# gadget_pcb.net
KiCad netlist of a schematic drawn in EAGLE
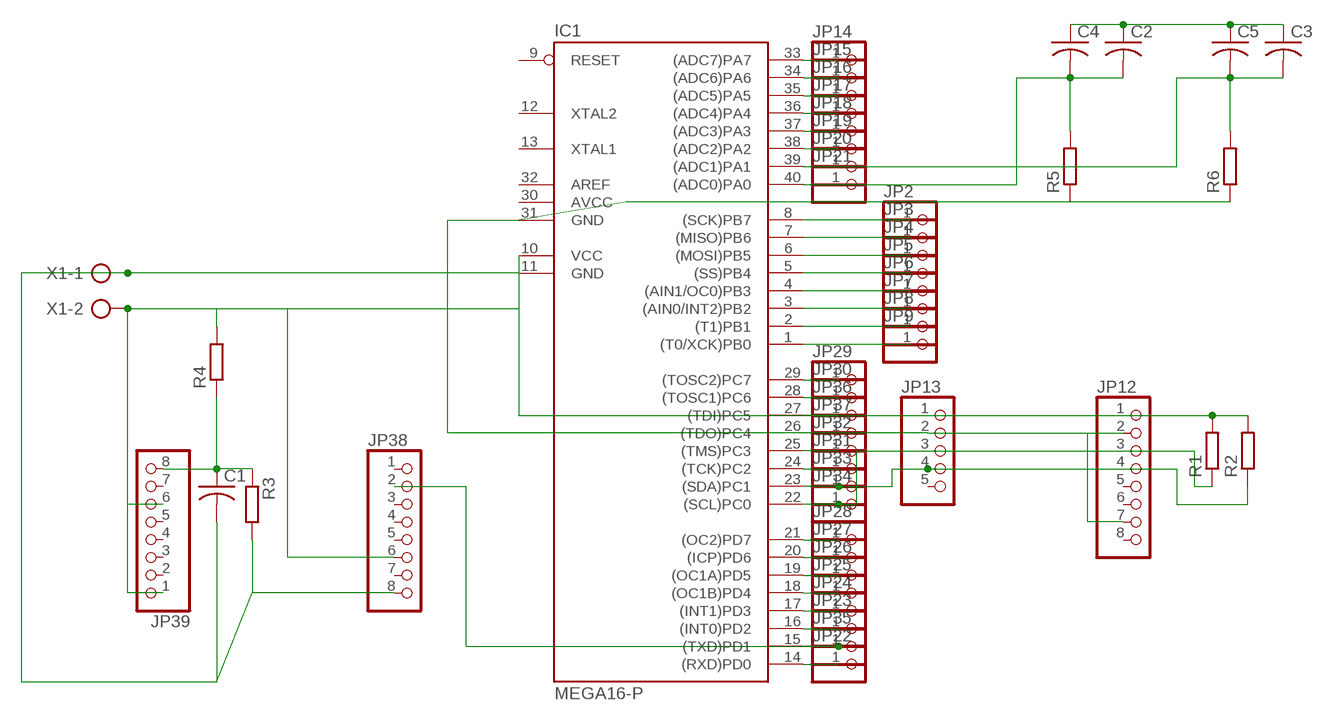
[diagram p0: schematic, sheet 1]

(export (version "E")
  (design (tool "Eeschema 10.0.6"))
  (components
    (comp (ref "C1")
      (value "C-US050-024X044")
      (footprint "eagle-import:C050-024X044")
      (libsource (lib "eagle-import") (part "C-US050-024X044"))
    )
    (comp (ref "C2")
      (value "C-US050-024X044")
      (footprint "eagle-import:C050-024X044")
      (libsource (lib "eagle-import") (part "C-US050-024X044"))
    )
    (comp (ref "C3")
      (value "C-US050-024X044")
      (footprint "eagle-import:C050-024X044")
      (libsource (lib "eagle-import") (part "C-US050-024X044"))
    )
    (comp (ref "C4")
      (value "C-US050-045X075")
      (footprint "eagle-import:C050-045X075")
      (libsource (lib "eagle-import") (part "C-US050-045X075"))
    )
    (comp (ref "C5")
      (value "C-US050-045X075")
      (footprint "eagle-import:C050-045X075")
      (libsource (lib "eagle-import") (part "C-US050-045X075"))
    )
    (comp (ref "IC1")
      (value "MEGA16-P")
      (footprint "eagle-import:DIL40")
      (fields (field (name "MPN") "ATMEGA16-16PU"))
      (libsource (lib "eagle-import") (part "MEGA16-P"))
    )
    (comp (ref "JP2")
      (value "PINHD-1X1")
      (footprint "eagle-import:1X01")
      (libsource (lib "eagle-import") (part "PINHD-1X1"))
    )
    (comp (ref "JP3")
      (value "PINHD-1X1")
      (footprint "eagle-import:1X01")
      (libsource (lib "eagle-import") (part "PINHD-1X1"))
    )
    (comp (ref "JP4")
      (value "PINHD-1X1")
      (footprint "eagle-import:1X01")
      (libsource (lib "eagle-import") (part "PINHD-1X1"))
    )
    (comp (ref "JP5")
      (value "PINHD-1X1")
      (footprint "eagle-import:1X01")
      (libsource (lib "eagle-import") (part "PINHD-1X1"))
    )
    (comp (ref "JP6")
      (value "PINHD-1X1")
      (footprint "eagle-import:1X01")
      (libsource (lib "eagle-import") (part "PINHD-1X1"))
    )
    (comp (ref "JP7")
      (value "PINHD-1X1")
      (footprint "eagle-import:1X01")
      (libsource (lib "eagle-import") (part "PINHD-1X1"))
    )
    (comp (ref "JP8")
      (value "PINHD-1X1")
      (footprint "eagle-import:1X01")
      (libsource (lib "eagle-import") (part "PINHD-1X1"))
    )
    (comp (ref "JP9")
      (value "PINHD-1X1")
      (footprint "eagle-import:1X01")
      (libsource (lib "eagle-import") (part "PINHD-1X1"))
    )
    (comp (ref "JP12")
      (value "PINHD-1X8")
      (footprint "eagle-import:1X08")
      (libsource (lib "eagle-import") (part "PINHD-1X8"))
    )
    (comp (ref "JP13")
      (value "PINHD-1X5")
      (footprint "eagle-import:1X05")
      (libsource (lib "eagle-import") (part "PINHD-1X5"))
    )
    (comp (ref "JP14")
      (value "PINHD-1X1")
      (footprint "eagle-import:1X01")
      (libsource (lib "eagle-import") (part "PINHD-1X1"))
    )
    (comp (ref "JP15")
      (value "PINHD-1X1")
      (footprint "eagle-import:1X01")
      (libsource (lib "eagle-import") (part "PINHD-1X1"))
    )
    (comp (ref "JP16")
      (value "PINHD-1X1")
      (footprint "eagle-import:1X01")
      (libsource (lib "eagle-import") (part "PINHD-1X1"))
    )
    (comp (ref "JP17")
      (value "PINHD-1X1")
      (footprint "eagle-import:1X01")
      (libsource (lib "eagle-import") (part "PINHD-1X1"))
    )
    (comp (ref "JP18")
      (value "PINHD-1X1")
      (footprint "eagle-import:1X01")
      (libsource (lib "eagle-import") (part "PINHD-1X1"))
    )
    (comp (ref "JP19")
      (value "PINHD-1X1")
      (footprint "eagle-import:1X01")
      (libsource (lib "eagle-import") (part "PINHD-1X1"))
    )
    (comp (ref "JP20")
      (value "PINHD-1X1")
      (footprint "eagle-import:1X01")
      (libsource (lib "eagle-import") (part "PINHD-1X1"))
    )
    (comp (ref "JP21")
      (value "PINHD-1X1")
      (footprint "eagle-import:1X01")
      (libsource (lib "eagle-import") (part "PINHD-1X1"))
    )
    (comp (ref "JP22")
      (value "PINHD-1X1")
      (footprint "eagle-import:1X01")
      (libsource (lib "eagle-import") (part "PINHD-1X1"))
    )
    (comp (ref "JP23")
      (value "PINHD-1X1")
      (footprint "eagle-import:1X01")
      (libsource (lib "eagle-import") (part "PINHD-1X1"))
    )
    (comp (ref "JP24")
      (value "PINHD-1X1")
      (footprint "eagle-import:1X01")
      (libsource (lib "eagle-import") (part "PINHD-1X1"))
    )
    (comp (ref "JP25")
      (value "PINHD-1X1")
      (footprint "eagle-import:1X01")
      (libsource (lib "eagle-import") (part "PINHD-1X1"))
    )
    (comp (ref "JP26")
      (value "PINHD-1X1")
      (footprint "eagle-import:1X01")
      (libsource (lib "eagle-import") (part "PINHD-1X1"))
    )
    (comp (ref "JP27")
      (value "PINHD-1X1")
      (footprint "eagle-import:1X01")
      (libsource (lib "eagle-import") (part "PINHD-1X1"))
    )
    (comp (ref "JP28")
      (value "PINHD-1X1")
      (footprint "eagle-import:1X01")
      (libsource (lib "eagle-import") (part "PINHD-1X1"))
    )
    (comp (ref "JP29")
      (value "PINHD-1X1")
      (footprint "eagle-import:1X01")
      (libsource (lib "eagle-import") (part "PINHD-1X1"))
    )
    (comp (ref "JP30")
      (value "PINHD-1X1")
      (footprint "eagle-import:1X01")
      (libsource (lib "eagle-import") (part "PINHD-1X1"))
    )
    (comp (ref "JP31")
      (value "PINHD-1X1")
      (footprint "eagle-import:1X01")
      (libsource (lib "eagle-import") (part "PINHD-1X1"))
    )
    (comp (ref "JP32")
      (value "PINHD-1X1")
      (footprint "eagle-import:1X01")
      (libsource (lib "eagle-import") (part "PINHD-1X1"))
    )
    (comp (ref "JP33")
      (value "PINHD-1X1")
      (footprint "eagle-import:1X01")
      (libsource (lib "eagle-import") (part "PINHD-1X1"))
    )
    (comp (ref "JP34")
      (value "PINHD-1X1")
      (footprint "eagle-import:1X01")
      (libsource (lib "eagle-import") (part "PINHD-1X1"))
    )
    (comp (ref "JP35")
      (value "PINHD-1X1")
      (footprint "eagle-import:1X01")
      (libsource (lib "eagle-import") (part "PINHD-1X1"))
    )
    (comp (ref "JP36")
      (value "PINHD-1X1")
      (footprint "eagle-import:1X01")
      (libsource (lib "eagle-import") (part "PINHD-1X1"))
    )
    (comp (ref "JP37")
      (value "PINHD-1X1")
      (footprint "eagle-import:1X01")
      (libsource (lib "eagle-import") (part "PINHD-1X1"))
    )
    (comp (ref "JP38")
      (value "PINHD-1X8")
      (footprint "eagle-import:1X08")
      (libsource (lib "eagle-import") (part "PINHD-1X8"))
    )
    (comp (ref "JP39")
      (value "PINHD-1X8")
      (footprint "eagle-import:1X08")
      (libsource (lib "eagle-import") (part "PINHD-1X8"))
    )
    (comp (ref "R1")
      (value "R-EU_0207/10")
      (footprint "eagle-import:0207_10")
      (libsource (lib "eagle-import") (part "R-EU_0207/10"))
    )
    (comp (ref "R2")
      (value "R-EU_0207/10")
      (footprint "eagle-import:0207_10")
      (libsource (lib "eagle-import") (part "R-EU_0207/10"))
    )
    (comp (ref "R3")
      (value "R-EU_0207/5V")
      (footprint "eagle-import:0207_5V")
      (libsource (lib "eagle-import") (part "R-EU_0207/5V"))
    )
    (comp (ref "R4")
      (value "R-EU_0207/10")
      (footprint "eagle-import:0207_10")
      (libsource (lib "eagle-import") (part "R-EU_0207/10"))
    )
    (comp (ref "R5")
      (value "R-EU_0207/7")
      (footprint "eagle-import:0207_7")
      (libsource (lib "eagle-import") (part "R-EU_0207/7"))
    )
    (comp (ref "R6")
      (value "R-EU_0207/7")
      (footprint "eagle-import:0207_7")
      (libsource (lib "eagle-import") (part "R-EU_0207/7"))
    )
    (comp (ref "X1")
      (value "AK500/2")
      (footprint "eagle-import:AK500_2")
      (libsource (lib "eagle-import") (part "AK500/2"))
    )
  )
  (nets
    (net (code "1") (name "/AVCC") (class "Default")
      (node (ref "IC1") (pin "30") (pinfunction "AVCC_30") (pintype "power_in"))
    )
    (net (code "2") (name "Net-(C1-Pad1)") (class "Default")
      (node (ref "C1") (pin "1") (pinfunction "1_1") (pintype "passive"))
      (node (ref "JP39") (pin "8") (pinfunction "8_8") (pintype "passive"))
      (node (ref "R3") (pin "1") (pinfunction "1_1") (pintype "passive"))
      (node (ref "R4") (pin "1") (pinfunction "1_1") (pintype "passive"))
    )
    (net (code "3") (name "Net-(C2-Pad1)") (class "Default")
      (node (ref "C2") (pin "1") (pinfunction "1_1") (pintype "passive"))
      (node (ref "C3") (pin "1") (pinfunction "1_1") (pintype "passive"))
      (node (ref "C4") (pin "1") (pinfunction "1_1") (pintype "passive"))
      (node (ref "C5") (pin "1") (pinfunction "1_1") (pintype "passive"))
    )
    (net (code "4") (name "Net-(IC1-(ADC0)PA0)") (class "Default")
      (node (ref "C2") (pin "2") (pinfunction "2_2") (pintype "passive"))
      (node (ref "C4") (pin "2") (pinfunction "2_2") (pintype "passive"))
      (node (ref "IC1") (pin "40") (pinfunction "(ADC0)PA0_40") (pintype "bidirectional"))
      (node (ref "JP21") (pin "1") (pinfunction "1_1") (pintype "passive"))
      (node (ref "R5") (pin "2") (pinfunction "2_2") (pintype "passive"))
    )
    (net (code "5") (name "Net-(IC1-(ADC1)PA1)") (class "Default")
      (node (ref "C3") (pin "2") (pinfunction "2_2") (pintype "passive"))
      (node (ref "C5") (pin "2") (pinfunction "2_2") (pintype "passive"))
      (node (ref "IC1") (pin "39") (pinfunction "(ADC1)PA1_39") (pintype "bidirectional"))
      (node (ref "JP20") (pin "1") (pinfunction "1_1") (pintype "passive"))
      (node (ref "R6") (pin "2") (pinfunction "2_2") (pintype "passive"))
    )
    (net (code "6") (name "Net-(IC1-(ADC2)PA2)") (class "Default")
      (node (ref "IC1") (pin "38") (pinfunction "(ADC2)PA2_38") (pintype "bidirectional"))
      (node (ref "JP19") (pin "1") (pinfunction "1_1") (pintype "passive"))
    )
    (net (code "7") (name "Net-(IC1-(ADC3)PA3)") (class "Default")
      (node (ref "IC1") (pin "37") (pinfunction "(ADC3)PA3_37") (pintype "bidirectional"))
      (node (ref "JP18") (pin "1") (pinfunction "1_1") (pintype "passive"))
    )
    (net (code "8") (name "Net-(IC1-(ADC4)PA4)") (class "Default")
      (node (ref "IC1") (pin "36") (pinfunction "(ADC4)PA4_36") (pintype "bidirectional"))
      (node (ref "JP17") (pin "1") (pinfunction "1_1") (pintype "passive"))
    )
    (net (code "9") (name "Net-(IC1-(ADC5)PA5)") (class "Default")
      (node (ref "IC1") (pin "35") (pinfunction "(ADC5)PA5_35") (pintype "bidirectional"))
      (node (ref "JP16") (pin "1") (pinfunction "1_1") (pintype "passive"))
    )
    (net (code "10") (name "Net-(IC1-(ADC6)PA6)") (class "Default")
      (node (ref "IC1") (pin "34") (pinfunction "(ADC6)PA6_34") (pintype "bidirectional"))
      (node (ref "JP15") (pin "1") (pinfunction "1_1") (pintype "passive"))
    )
    (net (code "11") (name "Net-(IC1-(ADC7)PA7)") (class "Default")
      (node (ref "IC1") (pin "33") (pinfunction "(ADC7)PA7_33") (pintype "bidirectional"))
      (node (ref "JP14") (pin "1") (pinfunction "1_1") (pintype "passive"))
    )
    (net (code "12") (name "Net-(IC1-(AIN0{slash}INT2)PB2)") (class "Default")
      (node (ref "IC1") (pin "3") (pinfunction "(AIN0/INT2)PB2_3") (pintype "bidirectional"))
      (node (ref "JP7") (pin "1") (pinfunction "1_1") (pintype "passive"))
    )
    (net (code "13") (name "Net-(IC1-(AIN1{slash}OC0)PB3)") (class "Default")
      (node (ref "IC1") (pin "4") (pinfunction "(AIN1/OC0)PB3_4") (pintype "bidirectional"))
      (node (ref "JP6") (pin "1") (pinfunction "1_1") (pintype "passive"))
    )
    (net (code "14") (name "Net-(IC1-(ICP)PD6)") (class "Default")
      (node (ref "IC1") (pin "20") (pinfunction "(ICP)PD6_20") (pintype "bidirectional"))
      (node (ref "JP27") (pin "1") (pinfunction "1_1") (pintype "passive"))
    )
    (net (code "15") (name "Net-(IC1-(INT0)PD2)") (class "Default")
      (node (ref "IC1") (pin "16") (pinfunction "(INT0)PD2_16") (pintype "bidirectional"))
      (node (ref "JP23") (pin "1") (pinfunction "1_1") (pintype "passive"))
    )
    (net (code "16") (name "Net-(IC1-(INT1)PD3)") (class "Default")
      (node (ref "IC1") (pin "17") (pinfunction "(INT1)PD3_17") (pintype "bidirectional"))
      (node (ref "JP24") (pin "1") (pinfunction "1_1") (pintype "passive"))
    )
    (net (code "17") (name "Net-(IC1-(MISO)PB6)") (class "Default")
      (node (ref "IC1") (pin "7") (pinfunction "(MISO)PB6_7") (pintype "bidirectional"))
      (node (ref "JP3") (pin "1") (pinfunction "1_1") (pintype "passive"))
    )
    (net (code "18") (name "Net-(IC1-(MOSI)PB5)") (class "Default")
      (node (ref "IC1") (pin "6") (pinfunction "(MOSI)PB5_6") (pintype "bidirectional"))
      (node (ref "JP4") (pin "1") (pinfunction "1_1") (pintype "passive"))
    )
    (net (code "19") (name "Net-(IC1-(OC1A)PD5)") (class "Default")
      (node (ref "IC1") (pin "19") (pinfunction "(OC1A)PD5_19") (pintype "bidirectional"))
      (node (ref "JP26") (pin "1") (pinfunction "1_1") (pintype "passive"))
    )
    (net (code "20") (name "Net-(IC1-(OC1B)PD4)") (class "Default")
      (node (ref "IC1") (pin "18") (pinfunction "(OC1B)PD4_18") (pintype "bidirectional"))
      (node (ref "JP25") (pin "1") (pinfunction "1_1") (pintype "passive"))
    )
    (net (code "21") (name "Net-(IC1-(OC2)PD7)") (class "Default")
      (node (ref "IC1") (pin "21") (pinfunction "(OC2)PD7_21") (pintype "bidirectional"))
      (node (ref "JP28") (pin "1") (pinfunction "1_1") (pintype "passive"))
    )
    (net (code "22") (name "Net-(IC1-(RXD)PD0)") (class "Default")
      (node (ref "IC1") (pin "14") (pinfunction "(RXD)PD0_14") (pintype "bidirectional"))
      (node (ref "JP22") (pin "1") (pinfunction "1_1") (pintype "passive"))
    )
    (net (code "23") (name "Net-(IC1-(SCK)PB7)") (class "Default")
      (node (ref "IC1") (pin "8") (pinfunction "(SCK)PB7_8") (pintype "bidirectional"))
      (node (ref "JP2") (pin "1") (pinfunction "1_1") (pintype "passive"))
    )
    (net (code "24") (name "Net-(IC1-(SCL)PC0)") (class "Default")
      (node (ref "IC1") (pin "22") (pinfunction "(SCL)PC0_22") (pintype "bidirectional"))
      (node (ref "JP12") (pin "3") (pinfunction "3_3") (pintype "passive"))
      (node (ref "JP13") (pin "3") (pinfunction "3_3") (pintype "passive"))
      (node (ref "JP34") (pin "1") (pinfunction "1_1") (pintype "passive"))
      (node (ref "R1") (pin "1") (pinfunction "1_1") (pintype "passive"))
    )
    (net (code "25") (name "Net-(IC1-(SDA)PC1)") (class "Default")
      (node (ref "IC1") (pin "23") (pinfunction "(SDA)PC1_23") (pintype "bidirectional"))
      (node (ref "JP12") (pin "4") (pinfunction "4_4") (pintype "passive"))
      (node (ref "JP13") (pin "4") (pinfunction "4_4") (pintype "passive"))
      (node (ref "JP33") (pin "1") (pinfunction "1_1") (pintype "passive"))
      (node (ref "R2") (pin "1") (pinfunction "1_1") (pintype "passive"))
    )
    (net (code "26") (name "Net-(IC1-(SS)PB4)") (class "Default")
      (node (ref "IC1") (pin "5") (pinfunction "(SS)PB4_5") (pintype "bidirectional"))
      (node (ref "JP5") (pin "1") (pinfunction "1_1") (pintype "passive"))
    )
    (net (code "27") (name "Net-(IC1-(T0{slash}XCK)PB0)") (class "Default")
      (node (ref "IC1") (pin "1") (pinfunction "(T0/XCK)PB0_1") (pintype "bidirectional"))
      (node (ref "JP9") (pin "1") (pinfunction "1_1") (pintype "passive"))
    )
    (net (code "28") (name "Net-(IC1-(T1)PB1)") (class "Default")
      (node (ref "IC1") (pin "2") (pinfunction "(T1)PB1_2") (pintype "bidirectional"))
      (node (ref "JP8") (pin "1") (pinfunction "1_1") (pintype "passive"))
    )
    (net (code "29") (name "Net-(IC1-(TCK)PC2)") (class "Default")
      (node (ref "IC1") (pin "24") (pinfunction "(TCK)PC2_24") (pintype "bidirectional"))
      (node (ref "JP31") (pin "1") (pinfunction "1_1") (pintype "passive"))
    )
    (net (code "30") (name "Net-(IC1-(TDI)PC5)") (class "Default")
      (node (ref "IC1") (pin "27") (pinfunction "(TDI)PC5_27") (pintype "bidirectional"))
      (node (ref "JP36") (pin "1") (pinfunction "1_1") (pintype "passive"))
    )
    (net (code "31") (name "Net-(IC1-(TDO)PC4)") (class "Default")
      (node (ref "IC1") (pin "26") (pinfunction "(TDO)PC4_26") (pintype "bidirectional"))
      (node (ref "JP37") (pin "1") (pinfunction "1_1") (pintype "passive"))
    )
    (net (code "32") (name "Net-(IC1-(TMS)PC3)") (class "Default")
      (node (ref "IC1") (pin "25") (pinfunction "(TMS)PC3_25") (pintype "bidirectional"))
      (node (ref "JP32") (pin "1") (pinfunction "1_1") (pintype "passive"))
    )
    (net (code "33") (name "Net-(IC1-(TOSC1)PC6)") (class "Default")
      (node (ref "IC1") (pin "28") (pinfunction "(TOSC1)PC6_28") (pintype "bidirectional"))
      (node (ref "JP30") (pin "1") (pinfunction "1_1") (pintype "passive"))
    )
    (net (code "34") (name "Net-(IC1-(TOSC2)PC7)") (class "Default")
      (node (ref "IC1") (pin "29") (pinfunction "(TOSC2)PC7_29") (pintype "bidirectional"))
      (node (ref "JP29") (pin "1") (pinfunction "1_1") (pintype "passive"))
    )
    (net (code "35") (name "Net-(IC1-(TXD)PD1)") (class "Default")
      (node (ref "IC1") (pin "15") (pinfunction "(TXD)PD1_15") (pintype "bidirectional"))
      (node (ref "JP35") (pin "1") (pinfunction "1_1") (pintype "passive"))
      (node (ref "JP38") (pin "2") (pinfunction "2_2") (pintype "passive"))
    )
    (net (code "36") (name "Net-(IC1-VCC)") (class "Default")
      (node (ref "IC1") (pin "10") (pinfunction "VCC_10") (pintype "power_in"))
      (node (ref "JP12") (pin "1") (pinfunction "1_1") (pintype "passive"))
      (node (ref "JP13") (pin "1") (pinfunction "1_1") (pintype "passive"))
      (node (ref "JP38") (pin "6") (pinfunction "6_6") (pintype "passive"))
      (node (ref "JP39") (pin "1") (pinfunction "1_1") (pintype "passive"))
      (node (ref "JP39") (pin "6") (pinfunction "6_6") (pintype "passive"))
      (node (ref "R1") (pin "2") (pinfunction "2_2") (pintype "passive"))
      (node (ref "R2") (pin "2") (pinfunction "2_2") (pintype "passive"))
      (node (ref "R4") (pin "2") (pinfunction "2_2") (pintype "passive"))
      (node (ref "X1") (pin "2") (pinfunction "KL_2") (pintype "passive"))
    )
    (net (code "37") (name "Net-(X1A-KL)") (class "Default")
      (node (ref "C1") (pin "2") (pinfunction "2_2") (pintype "passive"))
      (node (ref "IC1") (pin "11") (pinfunction "GND_11") (pintype "power_in"))
      (node (ref "IC1") (pin "31") (pinfunction "GND_31") (pintype "power_in"))
      (node (ref "JP12") (pin "2") (pinfunction "2_2") (pintype "passive"))
      (node (ref "JP12") (pin "7") (pinfunction "7_7") (pintype "passive"))
      (node (ref "JP13") (pin "2") (pinfunction "2_2") (pintype "passive"))
      (node (ref "JP38") (pin "8") (pinfunction "8_8") (pintype "passive"))
      (node (ref "R3") (pin "2") (pinfunction "2_2") (pintype "passive"))
      (node (ref "R5") (pin "1") (pinfunction "1_1") (pintype "passive"))
      (node (ref "R6") (pin "1") (pinfunction "1_1") (pintype "passive"))
      (node (ref "X1") (pin "1") (pinfunction "KL_1") (pintype "passive"))
    )
    (net (code "38") (name "unconnected-(IC1-AREF-Pad32)") (class "Default")
      (node (ref "IC1") (pin "32") (pinfunction "AREF_32") (pintype "passive"))
    )
    (net (code "39") (name "unconnected-(IC1-RESET-Pad9)") (class "Default")
      (node (ref "IC1") (pin "9") (pinfunction "RESET_9") (pintype "input"))
    )
    (net (code "40") (name "unconnected-(IC1-XTAL1-Pad13)") (class "Default")
      (node (ref "IC1") (pin "13") (pinfunction "XTAL1_13") (pintype "bidirectional"))
    )
    (net (code "41") (name "unconnected-(IC1-XTAL2-Pad12)") (class "Default")
      (node (ref "IC1") (pin "12") (pinfunction "XTAL2_12") (pintype "bidirectional"))
    )
    (net (code "42") (name "unconnected-(JP12-Pad5)") (class "Default")
      (node (ref "JP12") (pin "5") (pinfunction "5_5") (pintype "passive"))
    )
    (net (code "43") (name "unconnected-(JP12-Pad6)") (class "Default")
      (node (ref "JP12") (pin "6") (pinfunction "6_6") (pintype "passive"))
    )
    (net (code "44") (name "unconnected-(JP12-Pad8)") (class "Default")
      (node (ref "JP12") (pin "8") (pinfunction "8_8") (pintype "passive"))
    )
    (net (code "45") (name "unconnected-(JP13-Pad5)") (class "Default")
      (node (ref "JP13") (pin "5") (pinfunction "5_5") (pintype "passive"))
    )
    (net (code "46") (name "unconnected-(JP38-Pad1)") (class "Default")
      (node (ref "JP38") (pin "1") (pinfunction "1_1") (pintype "passive"))
    )
    (net (code "47") (name "unconnected-(JP38-Pad3)") (class "Default")
      (node (ref "JP38") (pin "3") (pinfunction "3_3") (pintype "passive"))
    )
    (net (code "48") (name "unconnected-(JP38-Pad4)") (class "Default")
      (node (ref "JP38") (pin "4") (pinfunction "4_4") (pintype "passive"))
    )
    (net (code "49") (name "unconnected-(JP38-Pad5)") (class "Default")
      (node (ref "JP38") (pin "5") (pinfunction "5_5") (pintype "passive"))
    )
    (net (code "50") (name "unconnected-(JP38-Pad7)") (class "Default")
      (node (ref "JP38") (pin "7") (pinfunction "7_7") (pintype "passive"))
    )
    (net (code "51") (name "unconnected-(JP39-Pad2)") (class "Default")
      (node (ref "JP39") (pin "2") (pinfunction "2_2") (pintype "passive"))
    )
    (net (code "52") (name "unconnected-(JP39-Pad3)") (class "Default")
      (node (ref "JP39") (pin "3") (pinfunction "3_3") (pintype "passive"))
    )
    (net (code "53") (name "unconnected-(JP39-Pad4)") (class "Default")
      (node (ref "JP39") (pin "4") (pinfunction "4_4") (pintype "passive"))
    )
    (net (code "54") (name "unconnected-(JP39-Pad5)") (class "Default")
      (node (ref "JP39") (pin "5") (pinfunction "5_5") (pintype "passive"))
    )
    (net (code "55") (name "unconnected-(JP39-Pad7)") (class "Default")
      (node (ref "JP39") (pin "7") (pinfunction "7_7") (pintype "passive"))
    )
  )
)
